# Sheet1.net
KiCad netlist of a schematic drawn in Altium Designer
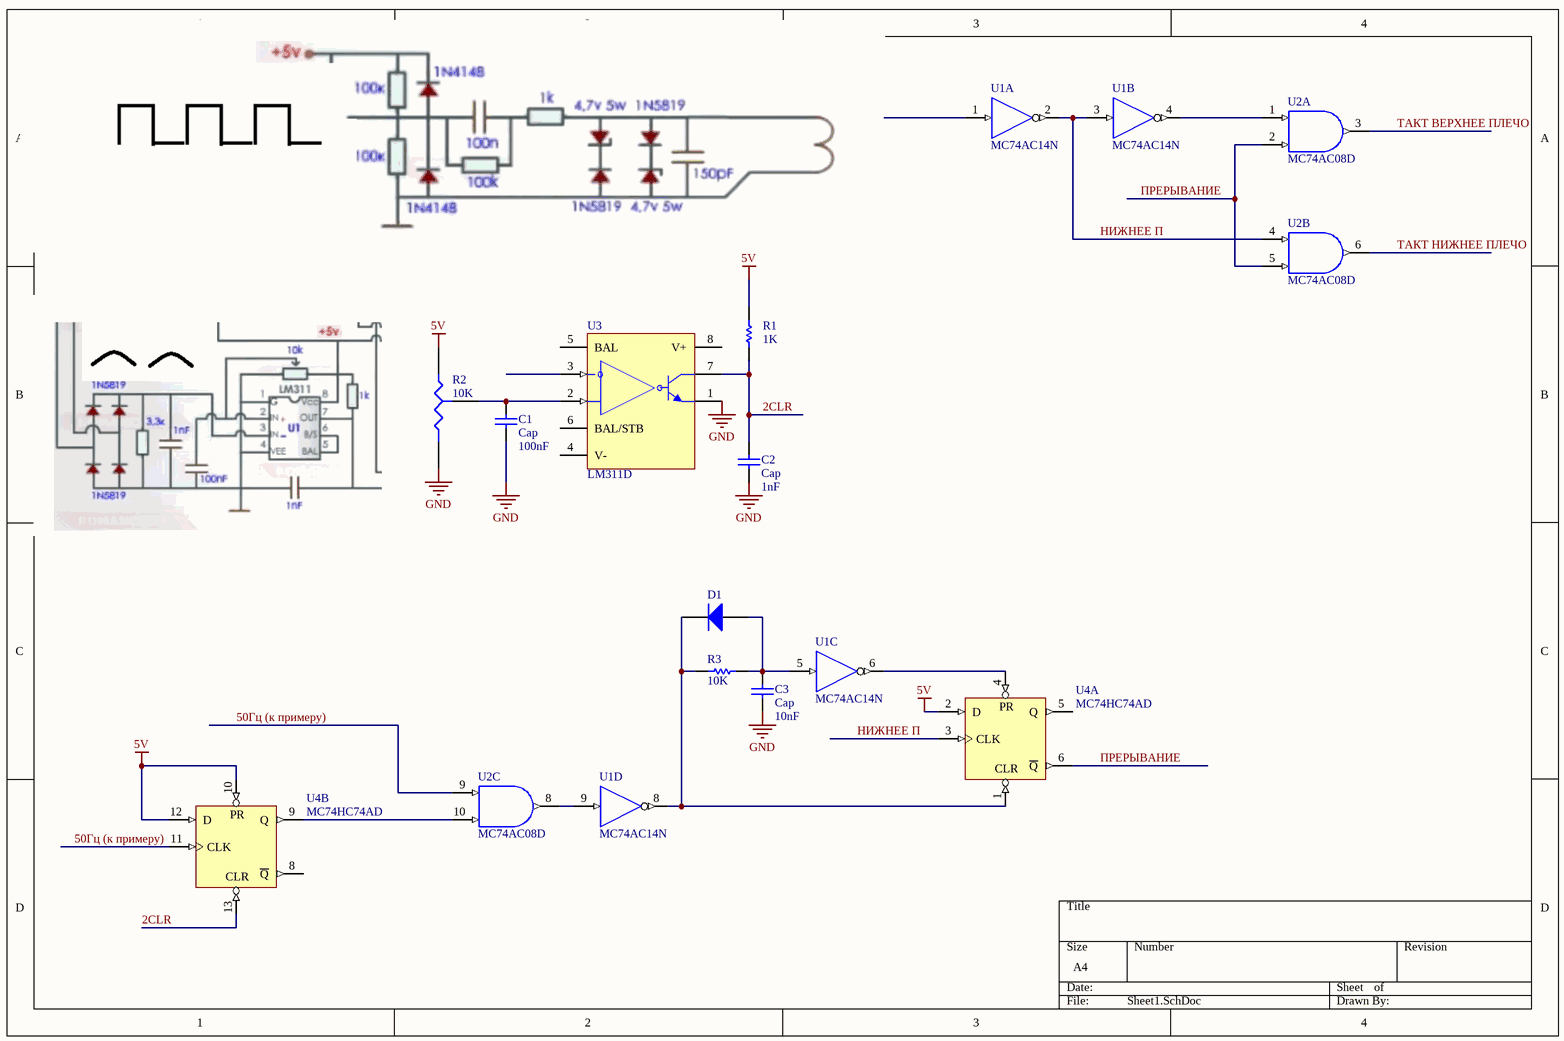
[diagram p0: Sheet1.SchDoc]

(export (version "E")
  (design (tool "Eeschema 10.0.6"))
  (components
    (comp (ref "C1")
      (value "Cap")
      (footprint "RAD-0.3")
      (description "Capacitor")
      (fields (field (name "ALTIUM_VALUE") "100nF") (field (name "PUBLISHER") "Altium Limited"))
      (libsource (lib "Miscellaneous Devices") (part "Cap"))
    )
    (comp (ref "C2")
      (value "Cap")
      (footprint "RAD-0.3")
      (description "Capacitor")
      (fields (field (name "ALTIUM_VALUE") "1nF") (field (name "PUBLISHER") "Altium Limited"))
      (libsource (lib "Miscellaneous Devices") (part "Cap"))
    )
    (comp (ref "C3")
      (value "Cap")
      (footprint "RAD-0.3")
      (description "Capacitor")
      (fields (field (name "ALTIUM_VALUE") "10nF") (field (name "PUBLISHER") "Altium Limited"))
      (libsource (lib "Miscellaneous Devices") (part "Cap"))
    )
    (comp (ref "D1")
      (value "Diode BAT18")
      (footprint "SOT-23_N")
      (description "Low-Loss RF Switching Diode")
      (fields (field (name "PUBLISHER") "Altium Limited"))
      (libsource (lib "Miscellaneous Devices") (part "Diode BAT18"))
    )
    (comp (ref "R1")
      (value "1K")
      (footprint "AXIAL-0.3")
      (description "Resistor")
      (fields (field (name "Comment") "Res1") (field (name "PUBLISHER") "Altium Limited"))
      (libsource (lib "Miscellaneous Devices") (part "Res1"))
    )
    (comp (ref "R2")
      (value "10K")
      (footprint "VR3")
      (description "Tapped Resistor")
      (fields (field (name "Comment") "Res Tap") (field (name "PUBLISHER") "Altium Limited"))
      (libsource (lib "Miscellaneous Devices") (part "Res Tap"))
    )
    (comp (ref "R3")
      (value "10K")
      (footprint "AXIAL-0.3")
      (description "Resistor")
      (fields (field (name "Comment") "Res1") (field (name "PUBLISHER") "Altium Limited"))
      (libsource (lib "Miscellaneous Devices") (part "Res1"))
    )
    (comp (ref "U1")
      (value "MC74AC14N")
      (footprint "646-06")
      (description "Hex Schmitt-Trigger Inverter")
      (fields (field (name "PUBLISHER") "Altium Limited"))
      (libsource (lib "ON Semi Logic Buffer Line Driver") (part "MC74AC14N"))
    )
    (comp (ref "U2")
      (value "MC74AC08D")
      (footprint "751A-03_N")
      (description "Quad 2-Input AND Gate")
      (fields (field (name "PUBLISHER") "Altium Limited"))
      (libsource (lib "ON Semi Logic Gate") (part "MC74AC08D"))
    )
    (comp (ref "U3")
      (value "LM311D")
      (footprint "D008_N")
      (description "Differential Comparator with Strobes")
      (fields (field (name "PUBLISHER") "Altium Limited"))
      (libsource (lib "TI Logic Comparator") (part "LM311D"))
    )
    (comp (ref "U4")
      (value "MC74HC74AD")
      (footprint "751A-03_N")
      (description "Dual D-Type Flip-Flop with Set and Reset")
      (fields (field (name "PUBLISHER") "Altium Limited"))
      (libsource (lib "ON Semi Logic Flip-Flop") (part "MC74HC74AD"))
    )
  )
  (nets
    (net (code "1") (name "/2CLR") (class "Default")
      (node (ref "C2") (pin "2") (pinfunction "2_2") (pintype "passive"))
      (node (ref "R1") (pin "1") (pinfunction "1_1") (pintype "passive"))
      (node (ref "U3") (pin "7") (pinfunction "COL_OUT_7") (pintype "passive"))
      (node (ref "U4") (pin "13") (pinfunction "CLR_13") (pintype "input"))
    )
    (net (code "2") (name "/50Гц (к примеру)") (class "Default")
      (node (ref "U2") (pin "9") (pinfunction "A_9") (pintype "input"))
      (node (ref "U4") (pin "11") (pinfunction "CLK_11") (pintype "input"))
    )
    (net (code "3") (name "/НИЖНЕЕ П") (class "Default")
      (node (ref "U1") (pin "2") (pinfunction "~{OUT}_2") (pintype "output"))
      (node (ref "U1") (pin "3") (pinfunction "IN_3") (pintype "input"))
      (node (ref "U2") (pin "4") (pinfunction "A_4") (pintype "input"))
      (node (ref "U4") (pin "3") (pinfunction "CLK_3") (pintype "input"))
    )
    (net (code "4") (name "/ПРЕРЫВАНИЕ") (class "Default")
      (node (ref "U2") (pin "2") (pinfunction "B_2") (pintype "input"))
      (node (ref "U2") (pin "5") (pinfunction "B_5") (pintype "input"))
      (node (ref "U4") (pin "6") (pinfunction "~{Q}_6") (pintype "output"))
    )
    (net (code "5") (name "/ТАКТ ВЕРХНЕЕ ПЛЕЧО") (class "Default")
      (node (ref "U2") (pin "3") (pinfunction "Y_3") (pintype "output"))
    )
    (net (code "6") (name "/ТАКТ НИЖНЕЕ ПЛЕЧО") (class "Default")
      (node (ref "U2") (pin "6") (pinfunction "Y_6") (pintype "output"))
    )
    (net (code "7") (name "5V") (class "Default")
      (node (ref "R1") (pin "2") (pinfunction "2_2") (pintype "passive"))
      (node (ref "R2") (pin "1") (pinfunction "A_1") (pintype "passive"))
      (node (ref "U4") (pin "10") (pinfunction "PR_10") (pintype "input"))
      (node (ref "U4") (pin "12") (pinfunction "D_12") (pintype "input"))
      (node (ref "U4") (pin "2") (pinfunction "D_2") (pintype "input"))
    )
    (net (code "8") (name "GND") (class "Default")
      (node (ref "C1") (pin "1") (pinfunction "1_1") (pintype "passive"))
      (node (ref "C2") (pin "1") (pinfunction "1_1") (pintype "passive"))
      (node (ref "C3") (pin "1") (pinfunction "1_1") (pintype "passive"))
      (node (ref "R2") (pin "2") (pinfunction "B_2") (pintype "passive"))
      (node (ref "U1") (pin "7") (pinfunction "GND_7") (pintype "power_in"))
      (node (ref "U2") (pin "7") (pinfunction "GND_7") (pintype "power_in"))
      (node (ref "U3") (pin "1") (pinfunction "EM_OUT_1") (pintype "passive"))
      (node (ref "U4") (pin "7") (pinfunction "GND_7") (pintype "power_in"))
    )
    (net (code "9") (name "Net-(D1-A)") (class "Default")
      (node (ref "C3") (pin "2") (pinfunction "2_2") (pintype "passive"))
      (node (ref "D1") (pin "1") (pinfunction "A_1") (pintype "passive"))
      (node (ref "R3") (pin "1") (pinfunction "1_1") (pintype "passive"))
      (node (ref "U1") (pin "5") (pinfunction "IN_5") (pintype "input"))
    )
    (net (code "10") (name "Net-(D1-K)") (class "Default")
      (node (ref "D1") (pin "3") (pinfunction "K_3") (pintype "passive"))
      (node (ref "R3") (pin "2") (pinfunction "2_2") (pintype "passive"))
      (node (ref "U1") (pin "8") (pinfunction "~{OUT}_8") (pintype "output"))
      (node (ref "U4") (pin "1") (pinfunction "CLR_1") (pintype "input"))
    )
    (net (code "11") (name "Net-(R2-TAP)") (class "Default")
      (node (ref "C1") (pin "2") (pinfunction "2_2") (pintype "passive"))
      (node (ref "R2") (pin "3") (pinfunction "TAP_3") (pintype "passive"))
      (node (ref "U3") (pin "2") (pinfunction "IN+_2") (pintype "input"))
    )
    (net (code "12") (name "Net-(U1B-~{OUT})") (class "Default")
      (node (ref "U1") (pin "4") (pinfunction "~{OUT}_4") (pintype "output"))
      (node (ref "U2") (pin "1") (pinfunction "A_1") (pintype "input"))
    )
    (net (code "13") (name "Net-(U1C-~{OUT})") (class "Default")
      (node (ref "U1") (pin "6") (pinfunction "~{OUT}_6") (pintype "output"))
      (node (ref "U4") (pin "4") (pinfunction "PR_4") (pintype "input"))
    )
    (net (code "14") (name "Net-(U1D-IN)") (class "Default")
      (node (ref "U1") (pin "9") (pinfunction "IN_9") (pintype "input"))
      (node (ref "U2") (pin "8") (pinfunction "Y_8") (pintype "output"))
    )
    (net (code "15") (name "Net-(U2C-B)") (class "Default")
      (node (ref "U2") (pin "10") (pinfunction "B_10") (pintype "input"))
      (node (ref "U4") (pin "9") (pinfunction "Q_9") (pintype "output"))
    )
    (net (code "16") (name "VDD") (class "Default")
      (node (ref "U1") (pin "14") (pinfunction "VDD_14") (pintype "power_in"))
      (node (ref "U2") (pin "14") (pinfunction "VDD_14") (pintype "power_in"))
      (node (ref "U4") (pin "14") (pinfunction "VDD_14") (pintype "power_in"))
    )
    (net (code "17") (name "unconnected-(U1A-IN-Pad1)") (class "Default")
      (node (ref "U1") (pin "1") (pinfunction "IN_1") (pintype "input"))
    )
    (net (code "18") (name "unconnected-(U3-BAL-Pad5)") (class "Default")
      (node (ref "U3") (pin "5") (pinfunction "BAL_5") (pintype "passive"))
    )
    (net (code "19") (name "unconnected-(U3-BAL{slash}STB-Pad6)") (class "Default")
      (node (ref "U3") (pin "6") (pinfunction "BAL/STB_6") (pintype "passive"))
    )
    (net (code "20") (name "unconnected-(U3-IN--Pad3)") (class "Default")
      (node (ref "U3") (pin "3") (pinfunction "IN-_3") (pintype "input"))
    )
    (net (code "21") (name "unconnected-(U3-V+-Pad8)") (class "Default")
      (node (ref "U3") (pin "8") (pinfunction "V+_8") (pintype "power_in"))
    )
    (net (code "22") (name "unconnected-(U3-V--Pad4)") (class "Default")
      (node (ref "U3") (pin "4") (pinfunction "V-_4") (pintype "power_in"))
    )
    (net (code "23") (name "unconnected-(U4A-Q-Pad5)") (class "Default")
      (node (ref "U4") (pin "5") (pinfunction "Q_5") (pintype "output"))
    )
    (net (code "24") (name "unconnected-(U4B-~{Q}-Pad8)") (class "Default")
      (node (ref "U4") (pin "8") (pinfunction "~{Q}_8") (pintype "output"))
    )
  )
)
